# 3phasecntrl-rev0.net
KiCad netlist of a schematic drawn in EAGLE
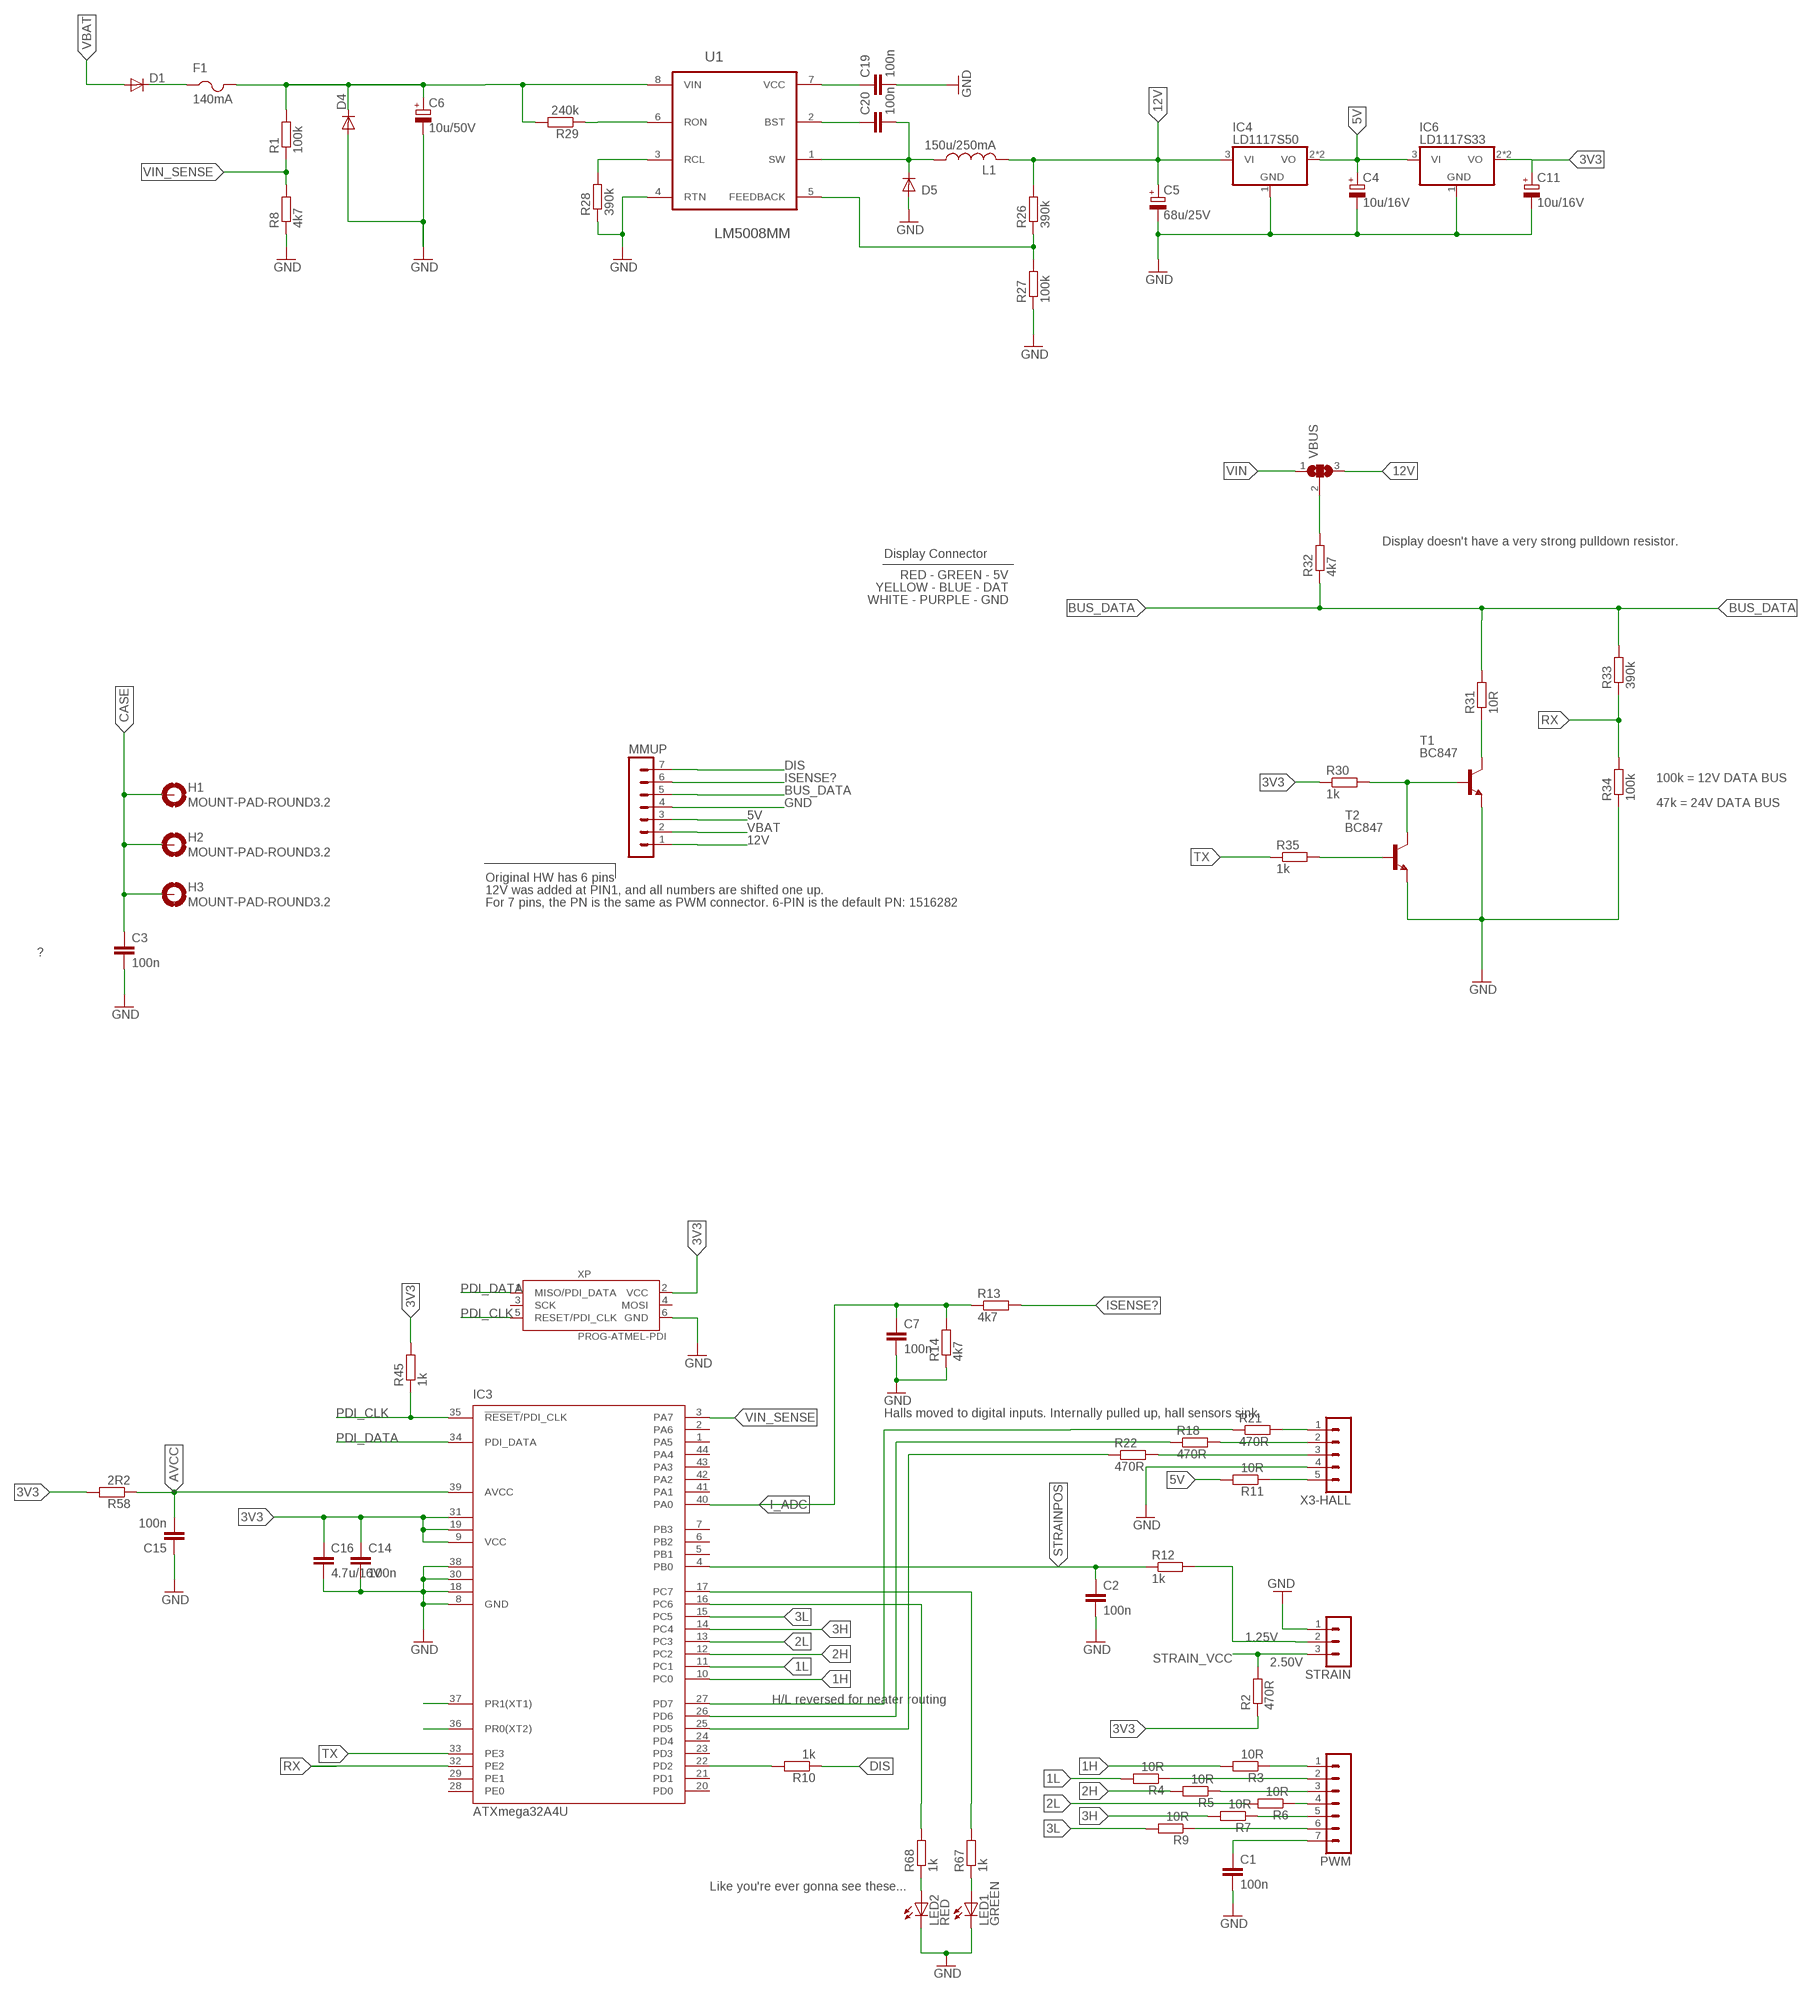
[diagram p0: schematic, sheet 1]

(export (version "E")
  (design (tool "Eeschema 10.0.6"))
  (components
    (comp (ref "C1")
      (value "100n")
      (footprint "eagle-import:C0805K")
      (libsource (lib "eagle-import") (part "C-EUC0805K"))
    )
    (comp (ref "C2")
      (value "100n")
      (footprint "eagle-import:C0805K")
      (libsource (lib "eagle-import") (part "C-EUC0805K"))
    )
    (comp (ref "C3")
      (value "100n")
      (footprint "eagle-import:C0805K")
      (libsource (lib "eagle-import") (part "C-EUC0805K"))
    )
    (comp (ref "C4")
      (value "10u/16V")
      (footprint "eagle-import:153CLV-0405")
      (libsource (lib "eagle-import") (part "CPOL-EU153CLV-0405"))
    )
    (comp (ref "C5")
      (value "68u/25V")
      (footprint "eagle-import:153CLV-0605")
      (libsource (lib "eagle-import") (part "CPOL-EU153CLV-0605"))
    )
    (comp (ref "C6")
      (value "10u/50V")
      (footprint "eagle-import:153CLV-0605")
      (libsource (lib "eagle-import") (part "CPOL-EU153CLV-0605"))
    )
    (comp (ref "C7")
      (value "100n")
      (footprint "eagle-import:C0805K")
      (libsource (lib "eagle-import") (part "C-EUC0805K"))
    )
    (comp (ref "C11")
      (value "10u/16V")
      (footprint "eagle-import:153CLV-0405")
      (libsource (lib "eagle-import") (part "CPOL-EU153CLV-0405"))
    )
    (comp (ref "C14")
      (value "100n")
      (footprint "eagle-import:C0805K")
      (libsource (lib "eagle-import") (part "C-EUC0805K"))
    )
    (comp (ref "C15")
      (value "100n")
      (footprint "eagle-import:C0805K")
      (libsource (lib "eagle-import") (part "C-EUC0805K"))
    )
    (comp (ref "C16")
      (value "4.7u/16V")
      (footprint "eagle-import:C0805K")
      (libsource (lib "eagle-import") (part "C-EUC0805K"))
    )
    (comp (ref "C19")
      (value "100n")
      (footprint "eagle-import:C0805K")
      (libsource (lib "eagle-import") (part "C-EUC0805K"))
    )
    (comp (ref "C20")
      (value "100n")
      (footprint "eagle-import:C0805K")
      (libsource (lib "eagle-import") (part "C-EUC0805K"))
    )
    (comp (ref "D1")
      (value "SS110B")
      (footprint "eagle-import:SMB")
      (libsource (lib "eagle-import") (part "DIODE-SMB"))
    )
    (comp (ref "D4")
      (value "SM6T39A")
      (footprint "eagle-import:SMB")
      (libsource (lib "eagle-import") (part "DIODE-SMB"))
    )
    (comp (ref "D5")
      (value "BAT46WH")
      (footprint "eagle-import:SOD323-W")
      (libsource (lib "eagle-import") (part "DIODE-SOD323-W"))
    )
    (comp (ref "F1")
      (value "140mA")
      (footprint "eagle-import:1812")
      (libsource (lib "eagle-import") (part "PTCFUSE-1812"))
    )
    (comp (ref "H1")
      (value "MOUNT-PAD-ROUND3.2")
      (footprint "eagle-import:3,2-PAD")
      (libsource (lib "eagle-import") (part "MOUNT-PAD-ROUND3.2"))
    )
    (comp (ref "H2")
      (value "MOUNT-PAD-ROUND3.2")
      (footprint "eagle-import:3,2-PAD")
      (libsource (lib "eagle-import") (part "MOUNT-PAD-ROUND3.2"))
    )
    (comp (ref "H3")
      (value "MOUNT-PAD-ROUND3.2")
      (footprint "eagle-import:3,2-PAD")
      (libsource (lib "eagle-import") (part "MOUNT-PAD-ROUND3.2"))
    )
    (comp (ref "IC3")
      (value "ATXmega32A4U")
      (footprint "eagle-import:TQFP44")
      (libsource (lib "eagle-import") (part "XMEGA16A4A"))
    )
    (comp (ref "IC4")
      (value "LD1117S50")
      (footprint "eagle-import:SOT223")
      (libsource (lib "eagle-import") (part "LM340?-STST"))
    )
    (comp (ref "IC6")
      (value "LD1117S33")
      (footprint "eagle-import:SOT223")
      (libsource (lib "eagle-import") (part "LM340?-STST"))
    )
    (comp (ref "L1")
      (value "150u/250mA")
      (footprint "eagle-import:POWER-CHOKE_WE-TPC")
      (libsource (lib "eagle-import") (part "L-USWE-TPC"))
    )
    (comp (ref "LED1")
      (value "GREEN")
      (footprint "eagle-import:CHIPLED_0805")
      (libsource (lib "eagle-import") (part "LEDCHIPLED_0805"))
    )
    (comp (ref "LED2")
      (value "RED")
      (footprint "eagle-import:CHIPLED_0805")
      (libsource (lib "eagle-import") (part "LEDCHIPLED_0805"))
    )
    (comp (ref "MMUP")
      (value "MA07-1")
      (footprint "eagle-import:MA07-1")
      (fields (field (name "OC_FARNELL") "unknown") (field (name "OC_NEWARK") "unknown"))
      (libsource (lib "eagle-import") (part "MA07-1"))
    )
    (comp (ref "PWM")
      (value "MA07-1")
      (footprint "eagle-import:MA07-1")
      (libsource (lib "eagle-import") (part "MA07-1"))
    )
    (comp (ref "R1")
      (value "100k")
      (footprint "eagle-import:M0805")
      (libsource (lib "eagle-import") (part "R-EU_M0805"))
    )
    (comp (ref "R2")
      (value "470R")
      (footprint "eagle-import:M0805")
      (libsource (lib "eagle-import") (part "R-EU_M0805"))
    )
    (comp (ref "R3")
      (value "10R")
      (footprint "eagle-import:M0805")
      (libsource (lib "eagle-import") (part "R-EU_M0805"))
    )
    (comp (ref "R4")
      (value "10R")
      (footprint "eagle-import:M0805")
      (libsource (lib "eagle-import") (part "R-EU_M0805"))
    )
    (comp (ref "R5")
      (value "10R")
      (footprint "eagle-import:M0805")
      (libsource (lib "eagle-import") (part "R-EU_M0805"))
    )
    (comp (ref "R6")
      (value "10R")
      (footprint "eagle-import:M0805")
      (libsource (lib "eagle-import") (part "R-EU_M0805"))
    )
    (comp (ref "R7")
      (value "10R")
      (footprint "eagle-import:M0805")
      (libsource (lib "eagle-import") (part "R-EU_M0805"))
    )
    (comp (ref "R8")
      (value "4k7")
      (footprint "eagle-import:M0805")
      (libsource (lib "eagle-import") (part "R-EU_M0805"))
    )
    (comp (ref "R9")
      (value "10R")
      (footprint "eagle-import:M0805")
      (libsource (lib "eagle-import") (part "R-EU_M0805"))
    )
    (comp (ref "R10")
      (value "1k")
      (footprint "eagle-import:M0805")
      (libsource (lib "eagle-import") (part "R-EU_M0805"))
    )
    (comp (ref "R11")
      (value "10R")
      (footprint "eagle-import:M0805")
      (libsource (lib "eagle-import") (part "R-EU_M0805"))
    )
    (comp (ref "R12")
      (value "1k")
      (footprint "eagle-import:M0805")
      (libsource (lib "eagle-import") (part "R-EU_M0805"))
    )
    (comp (ref "R13")
      (value "4k7")
      (footprint "eagle-import:M0805")
      (libsource (lib "eagle-import") (part "R-EU_M0805"))
    )
    (comp (ref "R14")
      (value "4k7")
      (footprint "eagle-import:M0805")
      (libsource (lib "eagle-import") (part "R-EU_M0805"))
    )
    (comp (ref "R18")
      (value "470R")
      (footprint "eagle-import:M0805")
      (libsource (lib "eagle-import") (part "R-EU_M0805"))
    )
    (comp (ref "R21")
      (value "470R")
      (footprint "eagle-import:M0805")
      (libsource (lib "eagle-import") (part "R-EU_M0805"))
    )
    (comp (ref "R22")
      (value "470R")
      (footprint "eagle-import:M0805")
      (libsource (lib "eagle-import") (part "R-EU_M0805"))
    )
    (comp (ref "R26")
      (value "390k")
      (footprint "eagle-import:M0805")
      (libsource (lib "eagle-import") (part "R-EU_M0805"))
    )
    (comp (ref "R27")
      (value "100k")
      (footprint "eagle-import:M0805")
      (libsource (lib "eagle-import") (part "R-EU_M0805"))
    )
    (comp (ref "R28")
      (value "390k")
      (footprint "eagle-import:M0805")
      (libsource (lib "eagle-import") (part "R-EU_M0805"))
    )
    (comp (ref "R29")
      (value "240k")
      (footprint "eagle-import:M0805")
      (libsource (lib "eagle-import") (part "R-EU_M0805"))
    )
    (comp (ref "R30")
      (value "1k")
      (footprint "eagle-import:M0805")
      (libsource (lib "eagle-import") (part "R-EU_M0805"))
    )
    (comp (ref "R31")
      (value "10R")
      (footprint "eagle-import:M0805")
      (libsource (lib "eagle-import") (part "R-EU_M0805"))
    )
    (comp (ref "R32")
      (value "4k7")
      (footprint "eagle-import:M0805")
      (libsource (lib "eagle-import") (part "R-EU_M0805"))
    )
    (comp (ref "R33")
      (value "390k")
      (footprint "eagle-import:M0805")
      (libsource (lib "eagle-import") (part "R-EU_M0805"))
    )
    (comp (ref "R34")
      (value "100k")
      (footprint "eagle-import:M0805")
      (libsource (lib "eagle-import") (part "R-EU_M0805"))
    )
    (comp (ref "R35")
      (value "1k")
      (footprint "eagle-import:M0805")
      (libsource (lib "eagle-import") (part "R-EU_M0805"))
    )
    (comp (ref "R45")
      (value "1k")
      (footprint "eagle-import:M0805")
      (libsource (lib "eagle-import") (part "R-EU_M0805"))
    )
    (comp (ref "R58")
      (value "2R2")
      (footprint "eagle-import:M0805")
      (libsource (lib "eagle-import") (part "R-EU_M0805"))
    )
    (comp (ref "R67")
      (value "1k")
      (footprint "eagle-import:M0805")
      (libsource (lib "eagle-import") (part "R-EU_M0805"))
    )
    (comp (ref "R68")
      (value "1k")
      (footprint "eagle-import:M0805")
      (libsource (lib "eagle-import") (part "R-EU_M0805"))
    )
    (comp (ref "STRAIN")
      (value "MA03-1")
      (footprint "eagle-import:MA03-1")
      (libsource (lib "eagle-import") (part "MA03-1"))
    )
    (comp (ref "T1")
      (value "BC847")
      (footprint "eagle-import:SOT23")
      (libsource (lib "eagle-import") (part "BC847"))
    )
    (comp (ref "T2")
      (value "BC847")
      (footprint "eagle-import:SOT23")
      (libsource (lib "eagle-import") (part "BC847"))
    )
    (comp (ref "U1")
      (value "LM5008MM")
      (footprint "eagle-import:SOP65P490X109-8N")
      (libsource (lib "eagle-import") (part "LM5008MM"))
    )
    (comp (ref "VBUS")
      (value "SJ2W")
      (footprint "eagle-import:SJ_2")
      (libsource (lib "eagle-import") (part "SJ2W"))
    )
    (comp (ref "X3-HALL")
      (value "MA05-1")
      (footprint "eagle-import:MA05-1")
      (libsource (lib "eagle-import") (part "MA05-1"))
    )
    (comp (ref "XP")
      (value "PROG-ATMEL-PDI")
      (footprint "eagle-import:6-LSTB2")
      (libsource (lib "eagle-import") (part "PROG-ATMEL-PDI"))
    )
  )
  (nets
    (net (code "1") (name "/PDI_CLK") (class "Default")
      (node (ref "IC3") (pin "35") (pinfunction "~{RESET}/PDI_CLK_35") (pintype "bidirectional"))
      (node (ref "R45") (pin "1") (pinfunction "1_1") (pintype "passive"))
      (node (ref "XP") (pin "5") (pinfunction "RESET/PDI_CLK_5") (pintype "bidirectional"))
    )
    (net (code "2") (name "/PDI_DATA") (class "Default")
      (node (ref "IC3") (pin "34") (pinfunction "PDI_DATA_34") (pintype "bidirectional"))
      (node (ref "XP") (pin "1") (pinfunction "MISO/PDI_DATA_1") (pintype "bidirectional"))
    )
    (net (code "3") (name "/STRAIN_VCC") (class "Default")
      (node (ref "R2") (pin "2") (pinfunction "2_2") (pintype "passive"))
      (node (ref "STRAIN") (pin "3") (pinfunction "3_3") (pintype "passive"))
    )
    (net (code "4") (name "1H") (class "Default")
      (node (ref "IC3") (pin "10") (pinfunction "PC0_10") (pintype "bidirectional"))
      (node (ref "R3") (pin "2") (pinfunction "2_2") (pintype "passive"))
    )
    (net (code "5") (name "1L") (class "Default")
      (node (ref "IC3") (pin "11") (pinfunction "PC1_11") (pintype "bidirectional"))
      (node (ref "R4") (pin "2") (pinfunction "2_2") (pintype "passive"))
    )
    (net (code "6") (name "2H") (class "Default")
      (node (ref "IC3") (pin "12") (pinfunction "PC2_12") (pintype "bidirectional"))
      (node (ref "R5") (pin "2") (pinfunction "2_2") (pintype "passive"))
    )
    (net (code "7") (name "2L") (class "Default")
      (node (ref "IC3") (pin "13") (pinfunction "PC3_13") (pintype "bidirectional"))
      (node (ref "R6") (pin "2") (pinfunction "2_2") (pintype "passive"))
    )
    (net (code "8") (name "3H") (class "Default")
      (node (ref "IC3") (pin "14") (pinfunction "PC4_14") (pintype "bidirectional"))
      (node (ref "R7") (pin "2") (pinfunction "2_2") (pintype "passive"))
    )
    (net (code "9") (name "3L") (class "Default")
      (node (ref "IC3") (pin "15") (pinfunction "PC5_15") (pintype "bidirectional"))
      (node (ref "R9") (pin "2") (pinfunction "2_2") (pintype "passive"))
    )
    (net (code "10") (name "3V3") (class "Default")
      (node (ref "C11") (pin "+") (pinfunction "+_+") (pintype "passive"))
      (node (ref "C14") (pin "1") (pinfunction "1_1") (pintype "passive"))
      (node (ref "C16") (pin "1") (pinfunction "1_1") (pintype "passive"))
      (node (ref "IC3") (pin "19") (pinfunction "VCC1_19") (pintype "power_in"))
      (node (ref "IC3") (pin "31") (pinfunction "VCC2_31") (pintype "power_in"))
      (node (ref "IC3") (pin "9") (pinfunction "VCC_9") (pintype "power_in"))
      (node (ref "IC6") (pin "2") (pinfunction "VO_2") (pintype "passive"))
      (node (ref "IC6") (pin "4") (pinfunction "VO_4") (pintype "passive"))
      (node (ref "R2") (pin "1") (pinfunction "1_1") (pintype "passive"))
      (node (ref "R30") (pin "1") (pinfunction "1_1") (pintype "passive"))
      (node (ref "R45") (pin "2") (pinfunction "2_2") (pintype "passive"))
      (node (ref "R58") (pin "2") (pinfunction "2_2") (pintype "passive"))
      (node (ref "XP") (pin "2") (pinfunction "VCC_2") (pintype "bidirectional"))
    )
    (net (code "11") (name "5V") (class "Default")
      (node (ref "C4") (pin "+") (pinfunction "+_+") (pintype "passive"))
      (node (ref "IC4") (pin "2") (pinfunction "VO_2") (pintype "passive"))
      (node (ref "IC4") (pin "4") (pinfunction "VO_4") (pintype "passive"))
      (node (ref "IC6") (pin "3") (pinfunction "VI_3") (pintype "input"))
      (node (ref "MMUP") (pin "3") (pinfunction "3_3") (pintype "passive"))
      (node (ref "R11") (pin "2") (pinfunction "2_2") (pintype "passive"))
    )
    (net (code "12") (name "12V") (class "Default")
      (node (ref "C5") (pin "+") (pinfunction "+_+") (pintype "passive"))
      (node (ref "IC4") (pin "3") (pinfunction "VI_3") (pintype "input"))
      (node (ref "L1") (pin "2") (pinfunction "2_2") (pintype "passive"))
      (node (ref "MMUP") (pin "1") (pinfunction "1_1") (pintype "passive"))
      (node (ref "R26") (pin "2") (pinfunction "2_2") (pintype "passive"))
      (node (ref "VBUS") (pin "3") (pinfunction "3_3") (pintype "passive"))
    )
    (net (code "13") (name "AVCC") (class "Default")
      (node (ref "C15") (pin "2") (pinfunction "2_2") (pintype "passive"))
      (node (ref "IC3") (pin "39") (pinfunction "AVCC_39") (pintype "power_in"))
      (node (ref "R58") (pin "1") (pinfunction "1_1") (pintype "passive"))
    )
    (net (code "14") (name "BUS_DATA") (class "Default")
      (node (ref "MMUP") (pin "5") (pinfunction "5_5") (pintype "passive"))
      (node (ref "R31") (pin "2") (pinfunction "2_2") (pintype "passive"))
      (node (ref "R32") (pin "1") (pinfunction "1_1") (pintype "passive"))
      (node (ref "R33") (pin "2") (pinfunction "2_2") (pintype "passive"))
    )
    (net (code "15") (name "CASE") (class "Default")
      (node (ref "C3") (pin "1") (pinfunction "1_1") (pintype "passive"))
      (node (ref "H1") (pin "B3,2") (pinfunction "MOUNT_B3,2") (pintype "passive"))
      (node (ref "H2") (pin "B3,2") (pinfunction "MOUNT_B3,2") (pintype "passive"))
      (node (ref "H3") (pin "B3,2") (pinfunction "MOUNT_B3,2") (pintype "passive"))
    )
    (net (code "16") (name "DIS") (class "Default")
      (node (ref "MMUP") (pin "7") (pinfunction "7_7") (pintype "passive"))
      (node (ref "R10") (pin "1") (pinfunction "1_1") (pintype "passive"))
    )
    (net (code "17") (name "GND") (class "Default")
      (node (ref "C1") (pin "2") (pinfunction "2_2") (pintype "passive"))
      (node (ref "C11") (pin "-") (pinfunction "-_-") (pintype "passive"))
      (node (ref "C14") (pin "2") (pinfunction "2_2") (pintype "passive"))
      (node (ref "C15") (pin "1") (pinfunction "1_1") (pintype "passive"))
      (node (ref "C16") (pin "2") (pinfunction "2_2") (pintype "passive"))
      (node (ref "C19") (pin "2") (pinfunction "2_2") (pintype "passive"))
      (node (ref "C2") (pin "2") (pinfunction "2_2") (pintype "passive"))
      (node (ref "C3") (pin "2") (pinfunction "2_2") (pintype "passive"))
      (node (ref "C4") (pin "-") (pinfunction "-_-") (pintype "passive"))
      (node (ref "C5") (pin "-") (pinfunction "-_-") (pintype "passive"))
      (node (ref "C6") (pin "-") (pinfunction "-_-") (pintype "passive"))
      (node (ref "C7") (pin "2") (pinfunction "2_2") (pintype "passive"))
      (node (ref "D4") (pin "A") (pinfunction "A_A") (pintype "passive"))
      (node (ref "D5") (pin "A") (pinfunction "A_A") (pintype "passive"))
      (node (ref "IC3") (pin "18") (pinfunction "GND1_18") (pintype "power_in"))
      (node (ref "IC3") (pin "30") (pinfunction "GND2_30") (pintype "power_in"))
      (node (ref "IC3") (pin "38") (pinfunction "GND3_38") (pintype "power_in"))
      (node (ref "IC3") (pin "8") (pinfunction "GND_8") (pintype "power_in"))
      (node (ref "IC4") (pin "1") (pinfunction "GND_1") (pintype "passive"))
      (node (ref "IC6") (pin "1") (pinfunction "GND_1") (pintype "passive"))
      (node (ref "LED1") (pin "C") (pinfunction "C_C") (pintype "passive"))
      (node (ref "LED2") (pin "C") (pinfunction "C_C") (pintype "passive"))
      (node (ref "MMUP") (pin "4") (pinfunction "4_4") (pintype "passive"))
      (node (ref "R14") (pin "1") (pinfunction "1_1") (pintype "passive"))
      (node (ref "R27") (pin "1") (pinfunction "1_1") (pintype "passive"))
      (node (ref "R28") (pin "1") (pinfunction "1_1") (pintype "passive"))
      (node (ref "R34") (pin "1") (pinfunction "1_1") (pintype "passive"))
      (node (ref "R8") (pin "1") (pinfunction "1_1") (pintype "passive"))
      (node (ref "STRAIN") (pin "1") (pinfunction "1_1") (pintype "passive"))
      (node (ref "T1") (pin "2") (pinfunction "E_2") (pintype "passive"))
      (node (ref "T2") (pin "2") (pinfunction "E_2") (pintype "passive"))
      (node (ref "U1") (pin "4") (pinfunction "RTN_4") (pintype "passive"))
      (node (ref "X3-HALL") (pin "4") (pinfunction "4_4") (pintype "passive"))
      (node (ref "XP") (pin "6") (pinfunction "GND_6") (pintype "bidirectional"))
    )
    (net (code "18") (name "ISENSE?") (class "Default")
      (node (ref "MMUP") (pin "6") (pinfunction "6_6") (pintype "passive"))
      (node (ref "R13") (pin "2") (pinfunction "2_2") (pintype "passive"))
    )
    (net (code "19") (name "I_ADC") (class "Default")
      (node (ref "C7") (pin "1") (pinfunction "1_1") (pintype "passive"))
      (node (ref "IC3") (pin "40") (pinfunction "PA0_40") (pintype "bidirectional"))
      (node (ref "R13") (pin "1") (pinfunction "1_1") (pintype "passive"))
      (node (ref "R14") (pin "2") (pinfunction "2_2") (pintype "passive"))
    )
    (net (code "20") (name "Net-(C1-Pad1)") (class "Default")
      (node (ref "C1") (pin "1") (pinfunction "1_1") (pintype "passive"))
      (node (ref "PWM") (pin "7") (pinfunction "7_7") (pintype "passive"))
    )
    (net (code "21") (name "Net-(D1-PadC)") (class "Default")
      (node (ref "D1") (pin "C") (pinfunction "C_C") (pintype "passive"))
      (node (ref "F1") (pin "1") (pinfunction "1_1") (pintype "passive"))
    )
    (net (code "22") (name "Net-(IC3-PC6)") (class "Default")
      (node (ref "IC3") (pin "16") (pinfunction "PC6_16") (pintype "bidirectional"))
      (node (ref "R68") (pin "2") (pinfunction "2_2") (pintype "passive"))
    )
    (net (code "23") (name "Net-(IC3-PC7)") (class "Default")
      (node (ref "IC3") (pin "17") (pinfunction "PC7_17") (pintype "bidirectional"))
      (node (ref "R67") (pin "2") (pinfunction "2_2") (pintype "passive"))
    )
    (net (code "24") (name "Net-(IC3-PD2)") (class "Default")
      (node (ref "IC3") (pin "22") (pinfunction "PD2_22") (pintype "bidirectional"))
      (node (ref "R10") (pin "2") (pinfunction "2_2") (pintype "passive"))
    )
    (net (code "25") (name "Net-(IC3-PD5)") (class "Default")
      (node (ref "IC3") (pin "25") (pinfunction "PD5_25") (pintype "bidirectional"))
      (node (ref "R22") (pin "1") (pinfunction "1_1") (pintype "passive"))
    )
    (net (code "26") (name "Net-(IC3-PD6)") (class "Default")
      (node (ref "IC3") (pin "26") (pinfunction "PD6_26") (pintype "bidirectional"))
      (node (ref "R18") (pin "1") (pinfunction "1_1") (pintype "passive"))
    )
    (net (code "27") (name "Net-(IC3-PD7)") (class "Default")
      (node (ref "IC3") (pin "27") (pinfunction "PD7_27") (pintype "bidirectional"))
      (node (ref "R21") (pin "1") (pinfunction "1_1") (pintype "passive"))
    )
    (net (code "28") (name "Net-(LED1-PadA)") (class "Default")
      (node (ref "LED1") (pin "A") (pinfunction "A_A") (pintype "passive"))
      (node (ref "R67") (pin "1") (pinfunction "1_1") (pintype "passive"))
    )
    (net (code "29") (name "Net-(LED2-PadA)") (class "Default")
      (node (ref "LED2") (pin "A") (pinfunction "A_A") (pintype "passive"))
      (node (ref "R68") (pin "1") (pinfunction "1_1") (pintype "passive"))
    )
    (net (code "30") (name "Net-(PWM-Pad1)") (class "Default")
      (node (ref "PWM") (pin "1") (pinfunction "1_1") (pintype "passive"))
      (node (ref "R3") (pin "1") (pinfunction "1_1") (pintype "passive"))
    )
    (net (code "31") (name "Net-(PWM-Pad2)") (class "Default")
      (node (ref "PWM") (pin "2") (pinfunction "2_2") (pintype "passive"))
      (node (ref "R4") (pin "1") (pinfunction "1_1") (pintype "passive"))
    )
    (net (code "32") (name "Net-(PWM-Pad3)") (class "Default")
      (node (ref "PWM") (pin "3") (pinfunction "3_3") (pintype "passive"))
      (node (ref "R5") (pin "1") (pinfunction "1_1") (pintype "passive"))
    )
    (net (code "33") (name "Net-(PWM-Pad4)") (class "Default")
      (node (ref "PWM") (pin "4") (pinfunction "4_4") (pintype "passive"))
      (node (ref "R6") (pin "1") (pinfunction "1_1") (pintype "passive"))
    )
    (net (code "34") (name "Net-(PWM-Pad5)") (class "Default")
      (node (ref "PWM") (pin "5") (pinfunction "5_5") (pintype "passive"))
      (node (ref "R7") (pin "1") (pinfunction "1_1") (pintype "passive"))
    )
    (net (code "35") (name "Net-(PWM-Pad6)") (class "Default")
      (node (ref "PWM") (pin "6") (pinfunction "6_6") (pintype "passive"))
      (node (ref "R9") (pin "1") (pinfunction "1_1") (pintype "passive"))
    )
    (net (code "36") (name "Net-(R11-Pad1)") (class "Default")
      (node (ref "R11") (pin "1") (pinfunction "1_1") (pintype "passive"))
      (node (ref "X3-HALL") (pin "5") (pinfunction "5_5") (pintype "passive"))
    )
    (net (code "37") (name "Net-(R12-Pad2)") (class "Default")
      (node (ref "R12") (pin "2") (pinfunction "2_2") (pintype "passive"))
      (node (ref "STRAIN") (pin "2") (pinfunction "2_2") (pintype "passive"))
    )
    (net (code "38") (name "Net-(R18-Pad2)") (class "Default")
      (node (ref "R18") (pin "2") (pinfunction "2_2") (pintype "passive"))
      (node (ref "X3-HALL") (pin "2") (pinfunction "2_2") (pintype "passive"))
    )
    (net (code "39") (name "Net-(R21-Pad2)") (class "Default")
      (node (ref "R21") (pin "2") (pinfunction "2_2") (pintype "passive"))
      (node (ref "X3-HALL") (pin "1") (pinfunction "1_1") (pintype "passive"))
    )
    (net (code "40") (name "Net-(R22-Pad2)") (class "Default")
      (node (ref "R22") (pin "2") (pinfunction "2_2") (pintype "passive"))
      (node (ref "X3-HALL") (pin "3") (pinfunction "3_3") (pintype "passive"))
    )
    (net (code "41") (name "Net-(R32-Pad2)") (class "Default")
      (node (ref "R32") (pin "2") (pinfunction "2_2") (pintype "passive"))
      (node (ref "VBUS") (pin "2") (pinfunction "2_2") (pintype "passive"))
    )
    (net (code "42") (name "Net-(T1-B)") (class "Default")
      (node (ref "R30") (pin "2") (pinfunction "2_2") (pintype "passive"))
      (node (ref "T1") (pin "1") (pinfunction "B_1") (pintype "passive"))
      (node (ref "T2") (pin "3") (pinfunction "C_3") (pintype "passive"))
    )
    (net (code "43") (name "Net-(T1-C)") (class "Default")
      (node (ref "R31") (pin "1") (pinfunction "1_1") (pintype "passive"))
      (node (ref "T1") (pin "3") (pinfunction "C_3") (pintype "passive"))
    )
    (net (code "44") (name "Net-(T2-B)") (class "Default")
      (node (ref "R35") (pin "2") (pinfunction "2_2") (pintype "passive"))
      (node (ref "T2") (pin "1") (pinfunction "B_1") (pintype "passive"))
    )
    (net (code "45") (name "Net-(U1-BST)") (class "Default")
      (node (ref "C20") (pin "1") (pinfunction "1_1") (pintype "passive"))
      (node (ref "U1") (pin "2") (pinfunction "BST_2") (pintype "passive"))
    )
    (net (code "46") (name "Net-(U1-FEEDBACK)") (class "Default")
      (node (ref "R26") (pin "1") (pinfunction "1_1") (pintype "passive"))
      (node (ref "R27") (pin "2") (pinfunction "2_2") (pintype "passive"))
      (node (ref "U1") (pin "5") (pinfunction "FEEDBACK_5") (pintype "input"))
    )
    (net (code "47") (name "Net-(U1-RCL)") (class "Default")
      (node (ref "R28") (pin "2") (pinfunction "2_2") (pintype "passive"))
      (node (ref "U1") (pin "3") (pinfunction "RCL_3") (pintype "passive"))
    )
    (net (code "48") (name "Net-(U1-RON)") (class "Default")
      (node (ref "R29") (pin "1") (pinfunction "1_1") (pintype "passive"))
      (node (ref "U1") (pin "6") (pinfunction "RON_6") (pintype "input"))
    )
    (net (code "49") (name "Net-(U1-SW)") (class "Default")
      (node (ref "C20") (pin "2") (pinfunction "2_2") (pintype "passive"))
      (node (ref "D5") (pin "C") (pinfunction "C_C") (pintype "passive"))
      (node (ref "L1") (pin "1") (pinfunction "1_1") (pintype "passive"))
      (node (ref "U1") (pin "1") (pinfunction "SW_1") (pintype "output"))
    )
    (net (code "50") (name "Net-(U1-VCC)") (class "Default")
      (node (ref "C19") (pin "1") (pinfunction "1_1") (pintype "passive"))
      (node (ref "U1") (pin "7") (pinfunction "VCC_7") (pintype "power_in"))
    )
    (net (code "51") (name "RX") (class "Default")
      (node (ref "IC3") (pin "32") (pinfunction "PE2_32") (pintype "bidirectional"))
      (node (ref "R33") (pin "1") (pinfunction "1_1") (pintype "passive"))
      (node (ref "R34") (pin "2") (pinfunction "2_2") (pintype "passive"))
    )
    (net (code "52") (name "STRAINPOS") (class "Default")
      (node (ref "C2") (pin "1") (pinfunction "1_1") (pintype "passive"))
      (node (ref "IC3") (pin "4") (pinfunction "PB0_4") (pintype "bidirectional"))
      (node (ref "R12") (pin "1") (pinfunction "1_1") (pintype "passive"))
    )
    (net (code "53") (name "TX") (class "Default")
      (node (ref "IC3") (pin "33") (pinfunction "PE3_33") (pintype "bidirectional"))
      (node (ref "R35") (pin "1") (pinfunction "1_1") (pintype "passive"))
    )
    (net (code "54") (name "VBAT") (class "Default")
      (node (ref "D1") (pin "A") (pinfunction "A_A") (pintype "passive"))
      (node (ref "MMUP") (pin "2") (pinfunction "2_2") (pintype "passive"))
    )
    (net (code "55") (name "VIN") (class "Default")
      (node (ref "C6") (pin "+") (pinfunction "+_+") (pintype "passive"))
      (node (ref "D4") (pin "C") (pinfunction "C_C") (pintype "passive"))
      (node (ref "F1") (pin "2") (pinfunction "2_2") (pintype "passive"))
      (node (ref "R1") (pin "2") (pinfunction "2_2") (pintype "passive"))
      (node (ref "R29") (pin "2") (pinfunction "2_2") (pintype "passive"))
      (node (ref "U1") (pin "8") (pinfunction "VIN_8") (pintype "power_in"))
      (node (ref "VBUS") (pin "1") (pinfunction "1_1") (pintype "passive"))
    )
    (net (code "56") (name "VIN_SENSE") (class "Default")
      (node (ref "IC3") (pin "3") (pinfunction "PA7_3") (pintype "bidirectional"))
      (node (ref "R1") (pin "1") (pinfunction "1_1") (pintype "passive"))
      (node (ref "R8") (pin "2") (pinfunction "2_2") (pintype "passive"))
    )
    (net (code "57") (name "unconnected-(IC3-PA1-Pad41)") (class "Default")
      (node (ref "IC3") (pin "41") (pinfunction "PA1_41") (pintype "bidirectional"))
    )
    (net (code "58") (name "unconnected-(IC3-PA2-Pad42)") (class "Default")
      (node (ref "IC3") (pin "42") (pinfunction "PA2_42") (pintype "bidirectional"))
    )
    (net (code "59") (name "unconnected-(IC3-PA3-Pad43)") (class "Default")
      (node (ref "IC3") (pin "43") (pinfunction "PA3_43") (pintype "bidirectional"))
    )
    (net (code "60") (name "unconnected-(IC3-PA4-Pad44)") (class "Default")
      (node (ref "IC3") (pin "44") (pinfunction "PA4_44") (pintype "bidirectional"))
    )
    (net (code "61") (name "unconnected-(IC3-PA5-Pad1)") (class "Default")
      (node (ref "IC3") (pin "1") (pinfunction "PA5_1") (pintype "bidirectional"))
    )
    (net (code "62") (name "unconnected-(IC3-PA6-Pad2)") (class "Default")
      (node (ref "IC3") (pin "2") (pinfunction "PA6_2") (pintype "bidirectional"))
    )
    (net (code "63") (name "unconnected-(IC3-PB1-Pad5)") (class "Default")
      (node (ref "IC3") (pin "5") (pinfunction "PB1_5") (pintype "bidirectional"))
    )
    (net (code "64") (name "unconnected-(IC3-PB2-Pad6)") (class "Default")
      (node (ref "IC3") (pin "6") (pinfunction "PB2_6") (pintype "bidirectional"))
    )
    (net (code "65") (name "unconnected-(IC3-PB3-Pad7)") (class "Default")
      (node (ref "IC3") (pin "7") (pinfunction "PB3_7") (pintype "bidirectional"))
    )
    (net (code "66") (name "unconnected-(IC3-PD0-Pad20)") (class "Default")
      (node (ref "IC3") (pin "20") (pinfunction "PD0_20") (pintype "bidirectional"))
    )
    (net (code "67") (name "unconnected-(IC3-PD1-Pad21)") (class "Default")
      (node (ref "IC3") (pin "21") (pinfunction "PD1_21") (pintype "bidirectional"))
    )
    (net (code "68") (name "unconnected-(IC3-PD3-Pad23)") (class "Default")
      (node (ref "IC3") (pin "23") (pinfunction "PD3_23") (pintype "bidirectional"))
    )
    (net (code "69") (name "unconnected-(IC3-PD4-Pad24)") (class "Default")
      (node (ref "IC3") (pin "24") (pinfunction "PD4_24") (pintype "bidirectional"))
    )
    (net (code "70") (name "unconnected-(IC3-PE0-Pad28)") (class "Default")
      (node (ref "IC3") (pin "28") (pinfunction "PE0_28") (pintype "bidirectional"))
    )
    (net (code "71") (name "unconnected-(IC3-PE1-Pad29)") (class "Default")
      (node (ref "IC3") (pin "29") (pinfunction "PE1_29") (pintype "bidirectional"))
    )
    (net (code "72") (name "unconnected-(IC3-PR0(XT2)-Pad36)") (class "Default")
      (node (ref "IC3") (pin "36") (pinfunction "PR0(XT2)_36") (pintype "bidirectional"))
    )
    (net (code "73") (name "unconnected-(IC3-PR1(XT1)-Pad37)") (class "Default")
      (node (ref "IC3") (pin "37") (pinfunction "PR1(XT1)_37") (pintype "bidirectional"))
    )
    (net (code "74") (name "unconnected-(XP-MOSI-Pad4)") (class "Default")
      (node (ref "XP") (pin "4") (pinfunction "MOSI_4") (pintype "bidirectional"))
    )
    (net (code "75") (name "unconnected-(XP-SCK-Pad3)") (class "Default")
      (node (ref "XP") (pin "3") (pinfunction "SCK_3") (pintype "bidirectional"))
    )
  )
)
